# HighPowerBiPolarStepperMotorSchem.net
KiCad netlist of a schematic drawn in Altium Designer
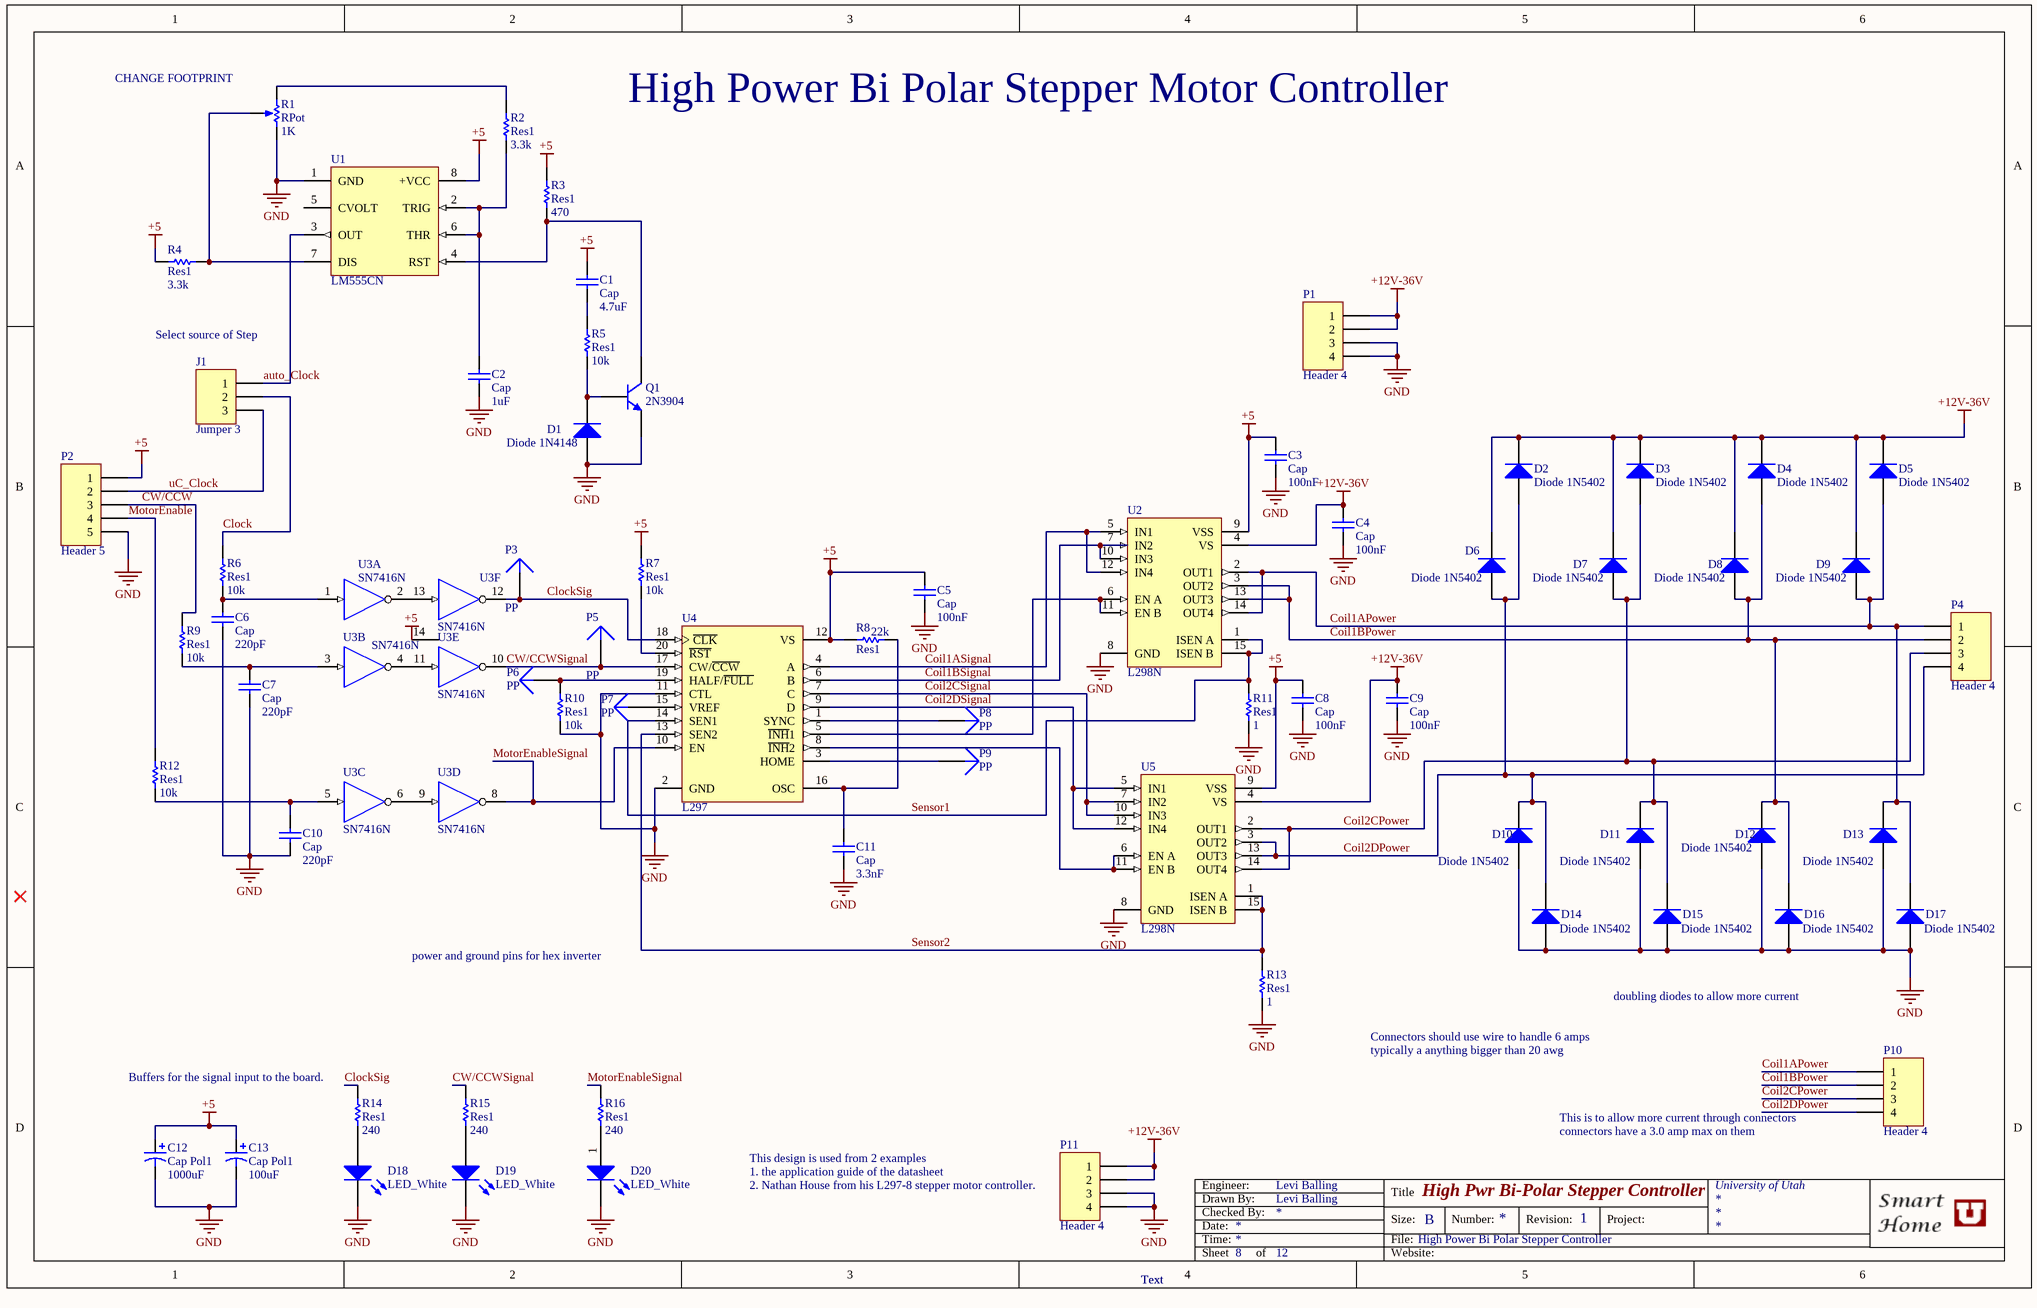
[diagram p0: HighPowerBiPolarStepperMotorSchem.SchDoc]

(export (version "E")
  (design (tool "Eeschema 10.0.6"))
  (components
    (comp (ref "C1")
      (value "Cap")
      (footprint "RAD-0.2")
      (description "Capacitor")
      (fields (field (name "ALTIUM_VALUE") "4.7uF") (field (name "PUBLISHER") "Altium Limited"))
      (libsource (lib "Miscellaneous Devices") (part "Cap"))
    )
    (comp (ref "C2")
      (value "Cap")
      (footprint "RAD-0.2")
      (description "Capacitor")
      (fields (field (name "ALTIUM_VALUE") "1uF") (field (name "PUBLISHER") "Altium Limited"))
      (libsource (lib "Miscellaneous Devices") (part "Cap"))
    )
    (comp (ref "C3")
      (value "Cap")
      (footprint "RAD-0.2")
      (description "Capacitor")
      (fields (field (name "ALTIUM_VALUE") "100nF") (field (name "PUBLISHER") "Altium Limited"))
      (libsource (lib "Miscellaneous Devices") (part "Cap"))
    )
    (comp (ref "C4")
      (value "Cap")
      (footprint "RAD-0.2")
      (description "Capacitor")
      (fields (field (name "ALTIUM_VALUE") "100nF") (field (name "PUBLISHER") "Altium Limited"))
      (libsource (lib "Miscellaneous Devices") (part "Cap"))
    )
    (comp (ref "C5")
      (value "Cap")
      (footprint "RAD-0.2")
      (description "Capacitor")
      (fields (field (name "ALTIUM_VALUE") "100nF") (field (name "PUBLISHER") "Altium Limited"))
      (libsource (lib "Miscellaneous Devices") (part "Cap"))
    )
    (comp (ref "C6")
      (value "Cap")
      (footprint "RAD-0.2")
      (description "Capacitor")
      (fields (field (name "ALTIUM_VALUE") "220pF") (field (name "PUBLISHER") "Altium Limited"))
      (libsource (lib "Miscellaneous Devices") (part "Cap"))
    )
    (comp (ref "C7")
      (value "Cap")
      (footprint "RAD-0.2")
      (description "Capacitor")
      (fields (field (name "ALTIUM_VALUE") "220pF") (field (name "PUBLISHER") "Altium Limited"))
      (libsource (lib "Miscellaneous Devices") (part "Cap"))
    )
    (comp (ref "C8")
      (value "Cap")
      (footprint "RAD-0.2")
      (description "Capacitor")
      (fields (field (name "ALTIUM_VALUE") "100nF") (field (name "PUBLISHER") "Altium Limited"))
      (libsource (lib "Miscellaneous Devices") (part "Cap"))
    )
    (comp (ref "C9")
      (value "Cap")
      (footprint "RAD-0.2")
      (description "Capacitor")
      (fields (field (name "ALTIUM_VALUE") "100nF") (field (name "PUBLISHER") "Altium Limited"))
      (libsource (lib "Miscellaneous Devices") (part "Cap"))
    )
    (comp (ref "C10")
      (value "Cap")
      (footprint "RAD-0.2")
      (description "Capacitor")
      (fields (field (name "ALTIUM_VALUE") "220pF") (field (name "PUBLISHER") "Altium Limited"))
      (libsource (lib "Miscellaneous Devices") (part "Cap"))
    )
    (comp (ref "C11")
      (value "Cap")
      (footprint "RAD-0.2")
      (description "Capacitor")
      (fields (field (name "ALTIUM_VALUE") "3.3nF") (field (name "PUBLISHER") "Altium Limited"))
      (libsource (lib "Miscellaneous Devices") (part "Cap"))
    )
    (comp (ref "C12")
      (value "Cap Pol1")
      (footprint "RB7.6-15")
      (description "Polarized Capacitor (Radial)")
      (fields (field (name "ALTIUM_VALUE") "1000uF") (field (name "PUBLISHER") "Altium Limited"))
      (libsource (lib "Miscellaneous Devices") (part "Cap Pol1"))
    )
    (comp (ref "C13")
      (value "Cap Pol1")
      (footprint "RB7.6-15")
      (description "Polarized Capacitor (Radial)")
      (fields (field (name "ALTIUM_VALUE") "100uF") (field (name "PUBLISHER") "Altium Limited"))
      (libsource (lib "Miscellaneous Devices") (part "Cap Pol1"))
    )
    (comp (ref "D1")
      (value "Diode 1N4148")
      (footprint "DO-35")
      (description "High Conductance Fast Diode")
      (fields (field (name "PUBLISHER") "Altium Limited"))
      (libsource (lib "Miscellaneous Devices") (part "Diode 1N4148"))
    )
    (comp (ref "D2")
      (value "Diode 1N5402")
      (footprint "DO-201AD")
      (description "3 Amp General Purpose Rectifier")
      (fields (field (name "PUBLISHER") "Altium Limited"))
      (libsource (lib "Miscellaneous Devices") (part "Diode 1N5402"))
    )
    (comp (ref "D3")
      (value "Diode 1N5402")
      (footprint "DO-201AD")
      (description "3 Amp General Purpose Rectifier")
      (fields (field (name "PUBLISHER") "Altium Limited"))
      (libsource (lib "Miscellaneous Devices") (part "Diode 1N5402"))
    )
    (comp (ref "D4")
      (value "Diode 1N5402")
      (footprint "DO-201AD")
      (description "3 Amp General Purpose Rectifier")
      (fields (field (name "PUBLISHER") "Altium Limited"))
      (libsource (lib "Miscellaneous Devices") (part "Diode 1N5402"))
    )
    (comp (ref "D5")
      (value "Diode 1N5402")
      (footprint "DO-201AD")
      (description "3 Amp General Purpose Rectifier")
      (fields (field (name "PUBLISHER") "Altium Limited"))
      (libsource (lib "Miscellaneous Devices") (part "Diode 1N5402"))
    )
    (comp (ref "D6")
      (value "Diode 1N5402")
      (footprint "DO-201AD")
      (description "3 Amp General Purpose Rectifier")
      (fields (field (name "PUBLISHER") "Altium Limited"))
      (libsource (lib "Miscellaneous Devices") (part "Diode 1N5402"))
    )
    (comp (ref "D7")
      (value "Diode 1N5402")
      (footprint "DO-201AD")
      (description "3 Amp General Purpose Rectifier")
      (fields (field (name "PUBLISHER") "Altium Limited"))
      (libsource (lib "Miscellaneous Devices") (part "Diode 1N5402"))
    )
    (comp (ref "D8")
      (value "Diode 1N5402")
      (footprint "DO-201AD")
      (description "3 Amp General Purpose Rectifier")
      (fields (field (name "PUBLISHER") "Altium Limited"))
      (libsource (lib "Miscellaneous Devices") (part "Diode 1N5402"))
    )
    (comp (ref "D9")
      (value "Diode 1N5402")
      (footprint "DO-201AD")
      (description "3 Amp General Purpose Rectifier")
      (fields (field (name "PUBLISHER") "Altium Limited"))
      (libsource (lib "Miscellaneous Devices") (part "Diode 1N5402"))
    )
    (comp (ref "D10")
      (value "Diode 1N5402")
      (footprint "DO-201AD")
      (description "3 Amp General Purpose Rectifier")
      (fields (field (name "PUBLISHER") "Altium Limited"))
      (libsource (lib "Miscellaneous Devices") (part "Diode 1N5402"))
    )
    (comp (ref "D11")
      (value "Diode 1N5402")
      (footprint "DO-201AD")
      (description "3 Amp General Purpose Rectifier")
      (fields (field (name "PUBLISHER") "Altium Limited"))
      (libsource (lib "Miscellaneous Devices") (part "Diode 1N5402"))
    )
    (comp (ref "D12")
      (value "Diode 1N5402")
      (footprint "DO-201AD")
      (description "3 Amp General Purpose Rectifier")
      (fields (field (name "PUBLISHER") "Altium Limited"))
      (libsource (lib "Miscellaneous Devices") (part "Diode 1N5402"))
    )
    (comp (ref "D13")
      (value "Diode 1N5402")
      (footprint "DO-201AD")
      (description "3 Amp General Purpose Rectifier")
      (fields (field (name "PUBLISHER") "Altium Limited"))
      (libsource (lib "Miscellaneous Devices") (part "Diode 1N5402"))
    )
    (comp (ref "D14")
      (value "Diode 1N5402")
      (footprint "DO-201AD")
      (description "3 Amp General Purpose Rectifier")
      (fields (field (name "PUBLISHER") "Altium Limited"))
      (libsource (lib "Miscellaneous Devices") (part "Diode 1N5402"))
    )
    (comp (ref "D15")
      (value "Diode 1N5402")
      (footprint "DO-201AD")
      (description "3 Amp General Purpose Rectifier")
      (fields (field (name "PUBLISHER") "Altium Limited"))
      (libsource (lib "Miscellaneous Devices") (part "Diode 1N5402"))
    )
    (comp (ref "D16")
      (value "Diode 1N5402")
      (footprint "DO-201AD")
      (description "3 Amp General Purpose Rectifier")
      (fields (field (name "PUBLISHER") "Altium Limited"))
      (libsource (lib "Miscellaneous Devices") (part "Diode 1N5402"))
    )
    (comp (ref "D17")
      (value "Diode 1N5402")
      (footprint "DO-201AD")
      (description "3 Amp General Purpose Rectifier")
      (fields (field (name "PUBLISHER") "Altium Limited"))
      (libsource (lib "Miscellaneous Devices") (part "Diode 1N5402"))
    )
    (comp (ref "D18")
      (value "LED_White")
      (footprint "LED")
      (description "Typical INFRARED GaAs LED")
      (fields (field (name "PUBLISHER") "Altium Limited"))
      (libsource (lib "Miscellaneous Devices") (part "LED0"))
    )
    (comp (ref "D19")
      (value "LED_White")
      (footprint "LED")
      (description "Typical INFRARED GaAs LED")
      (fields (field (name "PUBLISHER") "Altium Limited"))
      (libsource (lib "Miscellaneous Devices") (part "LED0"))
    )
    (comp (ref "D20")
      (value "LED_White")
      (footprint "LED")
      (description "Typical INFRARED GaAs LED")
      (fields (field (name "PUBLISHER") "Altium Limited"))
      (libsource (lib "") (part "LED0_1"))
    )
    (comp (ref "J1")
      (value "Jumper 3")
      (footprint "HDR1X3")
      (description "Header, 3-Pin")
      (fields (field (name "PUBLISHER") "Altium Limited"))
      (libsource (lib "Miscellaneous Connectors") (part "Header 3"))
    )
    (comp (ref "P1")
      (value "Header 4")
      (footprint "HDR1X4")
      (description "Header, 4-Pin")
      (fields (field (name "PUBLISHER") "Altium Limited"))
      (libsource (lib "Miscellaneous Connectors") (part "Header 4"))
    )
    (comp (ref "P2")
      (value "Header 5")
      (footprint "HDR1X5")
      (description "Header, 5-Pin")
      (fields (field (name "PUBLISHER") "Altium Limited"))
      (libsource (lib "Miscellaneous Connectors") (part "Header 5"))
    )
    (comp (ref "P3")
      (value "PP")
      (footprint "PIN1")
      (description "Plug")
      (fields (field (name "PUBLISHER") "Altium Limited"))
      (libsource (lib "Miscellaneous Connectors") (part "Plug"))
    )
    (comp (ref "P4")
      (value "Header 4")
      (footprint "HDR1X4")
      (description "Header, 4-Pin")
      (fields (field (name "PUBLISHER") "Altium Limited"))
      (libsource (lib "") (part "Header 4_1"))
    )
    (comp (ref "P5")
      (value "PP")
      (footprint "PIN1")
      (description "Plug")
      (fields (field (name "PUBLISHER") "Altium Limited"))
      (libsource (lib "Miscellaneous Connectors") (part "Plug"))
    )
    (comp (ref "P6")
      (value "PP")
      (footprint "PIN1")
      (description "Plug")
      (fields (field (name "PUBLISHER") "Altium Limited"))
      (libsource (lib "Miscellaneous Connectors") (part "Plug"))
    )
    (comp (ref "P7")
      (value "PP")
      (footprint "PIN1")
      (description "Plug")
      (fields (field (name "PUBLISHER") "Altium Limited"))
      (libsource (lib "Miscellaneous Connectors") (part "Plug"))
    )
    (comp (ref "P8")
      (value "PP")
      (footprint "PIN1")
      (description "Plug")
      (fields (field (name "PUBLISHER") "Altium Limited"))
      (libsource (lib "Miscellaneous Connectors") (part "Plug"))
    )
    (comp (ref "P9")
      (value "PP")
      (footprint "PIN1")
      (description "Plug")
      (fields (field (name "PUBLISHER") "Altium Limited"))
      (libsource (lib "Miscellaneous Connectors") (part "Plug"))
    )
    (comp (ref "P10")
      (value "Header 4")
      (footprint "HDR1X4")
      (description "Header, 4-Pin")
      (fields (field (name "PUBLISHER") "Altium Limited"))
      (libsource (lib "") (part "Header 4_1"))
    )
    (comp (ref "P11")
      (value "Header 4")
      (footprint "HDR1X4")
      (description "Header, 4-Pin")
      (fields (field (name "PUBLISHER") "Altium Limited"))
      (libsource (lib "Miscellaneous Connectors") (part "Header 4"))
    )
    (comp (ref "Q1")
      (value "2N3904")
      (footprint "2N3904")
      (description "NPN General Purpose Amplifier")
      (fields (field (name "PUBLISHER") "Altium Limited"))
      (libsource (lib "Miscellaneous Devices") (part "2N3904"))
    )
    (comp (ref "R1")
      (value "RPot")
      (footprint "Variable_Resistor")
      (description "Potentiometer")
      (fields (field (name "ALTIUM_VALUE") "1K") (field (name "PUBLISHER") "Altium Limited"))
      (libsource (lib "Miscellaneous Devices") (part "RPot"))
    )
    (comp (ref "R2")
      (value "Res1")
      (footprint "AXIAL-0.3")
      (description "Resistor")
      (fields (field (name "ALTIUM_VALUE") "3.3k") (field (name "PUBLISHER") "Altium Limited"))
      (libsource (lib "Miscellaneous Devices") (part "Res1"))
    )
    (comp (ref "R3")
      (value "Res1")
      (footprint "AXIAL-0.3")
      (description "Resistor")
      (fields (field (name "ALTIUM_VALUE") "470") (field (name "PUBLISHER") "Altium Limited"))
      (libsource (lib "Miscellaneous Devices") (part "Res1"))
    )
    (comp (ref "R4")
      (value "Res1")
      (footprint "AXIAL-0.3")
      (description "Resistor")
      (fields (field (name "ALTIUM_VALUE") "3.3k") (field (name "PUBLISHER") "Altium Limited"))
      (libsource (lib "Miscellaneous Devices") (part "Res1"))
    )
    (comp (ref "R5")
      (value "Res1")
      (footprint "AXIAL-0.3")
      (description "Resistor")
      (fields (field (name "ALTIUM_VALUE") "10k") (field (name "PUBLISHER") "Altium Limited"))
      (libsource (lib "Miscellaneous Devices") (part "Res1"))
    )
    (comp (ref "R6")
      (value "Res1")
      (footprint "AXIAL-0.3")
      (description "Resistor")
      (fields (field (name "ALTIUM_VALUE") "10k") (field (name "PUBLISHER") "Altium Limited"))
      (libsource (lib "Miscellaneous Devices") (part "Res1"))
    )
    (comp (ref "R7")
      (value "Res1")
      (footprint "AXIAL-0.3")
      (description "Resistor")
      (fields (field (name "ALTIUM_VALUE") "10k") (field (name "PUBLISHER") "Altium Limited"))
      (libsource (lib "Miscellaneous Devices") (part "Res1"))
    )
    (comp (ref "R8")
      (value "Res1")
      (footprint "AXIAL-0.3")
      (description "Resistor")
      (fields (field (name "ALTIUM_VALUE") "22k") (field (name "PUBLISHER") "Altium Limited"))
      (libsource (lib "Miscellaneous Devices") (part "Res1"))
    )
    (comp (ref "R9")
      (value "Res1")
      (footprint "AXIAL-0.3")
      (description "Resistor")
      (fields (field (name "ALTIUM_VALUE") "10k") (field (name "PUBLISHER") "Altium Limited"))
      (libsource (lib "Miscellaneous Devices") (part "Res1"))
    )
    (comp (ref "R10")
      (value "Res1")
      (footprint "AXIAL-0.3")
      (description "Resistor")
      (fields (field (name "ALTIUM_VALUE") "10k") (field (name "PUBLISHER") "Altium Limited"))
      (libsource (lib "Miscellaneous Devices") (part "Res1"))
    )
    (comp (ref "R11")
      (value "Res1")
      (footprint "AXIAL-1.0")
      (description "Resistor")
      (fields (field (name "ALTIUM_VALUE") "1") (field (name "PUBLISHER") "Altium Limited"))
      (libsource (lib "Miscellaneous Devices") (part "Res1"))
    )
    (comp (ref "R12")
      (value "Res1")
      (footprint "AXIAL-0.3")
      (description "Resistor")
      (fields (field (name "ALTIUM_VALUE") "10k") (field (name "PUBLISHER") "Altium Limited"))
      (libsource (lib "Miscellaneous Devices") (part "Res1"))
    )
    (comp (ref "R13")
      (value "Res1")
      (footprint "AXIAL-1.0")
      (description "Resistor")
      (fields (field (name "ALTIUM_VALUE") "1") (field (name "PUBLISHER") "Altium Limited"))
      (libsource (lib "Miscellaneous Devices") (part "Res1"))
    )
    (comp (ref "R14")
      (value "Res1")
      (footprint "AXIAL-0.3")
      (description "Resistor")
      (fields (field (name "ALTIUM_VALUE") "240") (field (name "PUBLISHER") "Altium Limited"))
      (libsource (lib "Miscellaneous Devices") (part "Res1"))
    )
    (comp (ref "R15")
      (value "Res1")
      (footprint "AXIAL-0.3")
      (description "Resistor")
      (fields (field (name "ALTIUM_VALUE") "240") (field (name "PUBLISHER") "Altium Limited"))
      (libsource (lib "Miscellaneous Devices") (part "Res1"))
    )
    (comp (ref "R16")
      (value "Res1")
      (footprint "AXIAL-0.3")
      (description "Resistor")
      (fields (field (name "ALTIUM_VALUE") "240") (field (name "PUBLISHER") "Altium Limited"))
      (libsource (lib "Miscellaneous Devices") (part "Res1"))
    )
    (comp (ref "U1")
      (value "LM555CN")
      (footprint "N08E")
      (description "Timer")
      (fields
        (field (name "MANUFACTURER") "National Semiconductor")
        (field (name "DIGIKEYPARTNUMBER") "LM555CNNS-ND")
        (field (name "PUBLISHER") "Altium Limited")
      )
      (libsource (lib "NSC Analog") (part "LM555CN"))
    )
    (comp (ref "U2")
      (value "L298N")
      (footprint "Multiwatt15V")
      (description "Dual Full Bridge Driver")
      (fields (field (name "PUBLISHER") "Altium Limited"))
      (libsource (lib "ST Interface DC Motor Controller") (part "L298N"))
    )
    (comp (ref "U3")
      (value "SN7416N")
      (footprint "N014")
      (description "Hex Inverter Buffer / Driver with High-Voltage Outputs")
      (fields (field (name "PUBLISHER") "Altium Limited"))
      (libsource (lib "TI Logic Gate 1") (part "SN7416N"))
    )
    (comp (ref "U4")
      (value "L297")
      (footprint "DIP20")
      (description "Stepper Motor Controller")
      (fields (field (name "PUBLISHER") "Altium Limited"))
      (libsource (lib "ST Interface Stepper Motor Controller") (part "L297"))
    )
    (comp (ref "U5")
      (value "L298N")
      (footprint "Multiwatt15V")
      (description "Dual Full Bridge Driver")
      (fields (field (name "PUBLISHER") "Altium Limited"))
      (libsource (lib "ST Interface DC Motor Controller") (part "L298N"))
    )
  )
  (nets
    (net (code "1") (name "+5") (class "Default")
      (node (ref "C1") (pin "2") (pinfunction "2_2") (pintype "passive"))
      (node (ref "C12") (pin "1") (pinfunction "1_1") (pintype "passive"))
      (node (ref "C13") (pin "1") (pinfunction "1_1") (pintype "passive"))
      (node (ref "C3") (pin "2") (pinfunction "2_2") (pintype "passive"))
      (node (ref "C5") (pin "2") (pinfunction "2_2") (pintype "passive"))
      (node (ref "C8") (pin "2") (pinfunction "2_2") (pintype "passive"))
      (node (ref "P2") (pin "1") (pinfunction "1_1") (pintype "passive"))
      (node (ref "R3") (pin "1") (pinfunction "1_1") (pintype "passive"))
      (node (ref "R4") (pin "2") (pinfunction "2_2") (pintype "passive"))
      (node (ref "R7") (pin "2") (pinfunction "2_2") (pintype "passive"))
      (node (ref "R8") (pin "1") (pinfunction "1_1") (pintype "passive"))
      (node (ref "U1") (pin "8") (pinfunction "+VCC_8") (pintype "power_in"))
      (node (ref "U2") (pin "9") (pinfunction "VSS_9") (pintype "power_in"))
      (node (ref "U3") (pin "14") (pinfunction "VCC_14") (pintype "power_in"))
      (node (ref "U4") (pin "12") (pinfunction "VS_12") (pintype "power_in"))
      (node (ref "U5") (pin "9") (pinfunction "VSS_9") (pintype "power_in"))
    )
    (net (code "2") (name "+12V-36V") (class "Default")
      (node (ref "C4") (pin "2") (pinfunction "2_2") (pintype "passive"))
      (node (ref "C9") (pin "2") (pinfunction "2_2") (pintype "passive"))
      (node (ref "D2") (pin "2") (pinfunction "K_2") (pintype "passive"))
      (node (ref "D3") (pin "2") (pinfunction "K_2") (pintype "passive"))
      (node (ref "D4") (pin "2") (pinfunction "K_2") (pintype "passive"))
      (node (ref "D5") (pin "2") (pinfunction "K_2") (pintype "passive"))
      (node (ref "D6") (pin "2") (pinfunction "K_2") (pintype "passive"))
      (node (ref "D7") (pin "2") (pinfunction "K_2") (pintype "passive"))
      (node (ref "D8") (pin "2") (pinfunction "K_2") (pintype "passive"))
      (node (ref "D9") (pin "2") (pinfunction "K_2") (pintype "passive"))
      (node (ref "P1") (pin "1") (pinfunction "1_1") (pintype "passive"))
      (node (ref "P1") (pin "2") (pinfunction "2_2") (pintype "passive"))
      (node (ref "P11") (pin "1") (pinfunction "1_1") (pintype "passive"))
      (node (ref "P11") (pin "2") (pinfunction "2_2") (pintype "passive"))
      (node (ref "U2") (pin "4") (pinfunction "VS_4") (pintype "power_in"))
      (node (ref "U5") (pin "4") (pinfunction "VS_4") (pintype "power_in"))
    )
    (net (code "3") (name "/CW{slash}CCW") (class "Default")
      (node (ref "P2") (pin "3") (pinfunction "3_3") (pintype "passive"))
      (node (ref "R9") (pin "1") (pinfunction "1_1") (pintype "passive"))
    )
    (net (code "4") (name "/CW{slash}CCWSignal") (class "Default")
      (node (ref "P5") (pin "1") (pinfunction "1_1") (pintype "passive"))
      (node (ref "R15") (pin "1") (pinfunction "1_1") (pintype "passive"))
      (node (ref "U3") (pin "10") (pinfunction "Y_10") (pintype "open_collector"))
      (node (ref "U4") (pin "17") (pinfunction "CW/~{CCW}_17") (pintype "input"))
    )
    (net (code "5") (name "/Clock") (class "Default")
      (node (ref "J1") (pin "2") (pinfunction "2_2") (pintype "passive"))
      (node (ref "R6") (pin "1") (pinfunction "1_1") (pintype "passive"))
    )
    (net (code "6") (name "/ClockSig") (class "Default")
      (node (ref "P3") (pin "1") (pinfunction "1_1") (pintype "passive"))
      (node (ref "R14") (pin "1") (pinfunction "1_1") (pintype "passive"))
      (node (ref "U3") (pin "12") (pinfunction "Y_12") (pintype "open_collector"))
      (node (ref "U4") (pin "18") (pinfunction "~{CLK}_18") (pintype "input"))
    )
    (net (code "7") (name "/Coil1APower") (class "Default")
      (node (ref "D13") (pin "2") (pinfunction "K_2") (pintype "passive"))
      (node (ref "D17") (pin "2") (pinfunction "K_2") (pintype "passive"))
      (node (ref "D5") (pin "1") (pinfunction "A_1") (pintype "passive"))
      (node (ref "D9") (pin "1") (pinfunction "A_1") (pintype "passive"))
      (node (ref "P10") (pin "1") (pinfunction "1_1") (pintype "passive"))
      (node (ref "P4") (pin "1") (pinfunction "1_1") (pintype "passive"))
      (node (ref "U2") (pin "14") (pinfunction "OUT4_14") (pintype "output"))
      (node (ref "U2") (pin "2") (pinfunction "OUT1_2") (pintype "output"))
    )
    (net (code "8") (name "/Coil1ASignal") (class "Default")
      (node (ref "U2") (pin "12") (pinfunction "IN4_12") (pintype "input"))
      (node (ref "U2") (pin "5") (pinfunction "IN1_5") (pintype "input"))
      (node (ref "U4") (pin "4") (pinfunction "A_4") (pintype "output"))
    )
    (net (code "9") (name "/Coil1BPower") (class "Default")
      (node (ref "D12") (pin "2") (pinfunction "K_2") (pintype "passive"))
      (node (ref "D16") (pin "2") (pinfunction "K_2") (pintype "passive"))
      (node (ref "D4") (pin "1") (pinfunction "A_1") (pintype "passive"))
      (node (ref "D8") (pin "1") (pinfunction "A_1") (pintype "passive"))
      (node (ref "P10") (pin "2") (pinfunction "2_2") (pintype "passive"))
      (node (ref "P4") (pin "2") (pinfunction "2_2") (pintype "passive"))
      (node (ref "U2") (pin "13") (pinfunction "OUT3_13") (pintype "output"))
      (node (ref "U2") (pin "3") (pinfunction "OUT2_3") (pintype "output"))
    )
    (net (code "10") (name "/Coil1BSignal") (class "Default")
      (node (ref "U2") (pin "10") (pinfunction "IN3_10") (pintype "input"))
      (node (ref "U2") (pin "7") (pinfunction "IN2_7") (pintype "input"))
      (node (ref "U4") (pin "6") (pinfunction "B_6") (pintype "output"))
    )
    (net (code "11") (name "/Coil2CPower") (class "Default")
      (node (ref "D11") (pin "2") (pinfunction "K_2") (pintype "passive"))
      (node (ref "D15") (pin "2") (pinfunction "K_2") (pintype "passive"))
      (node (ref "D3") (pin "1") (pinfunction "A_1") (pintype "passive"))
      (node (ref "D7") (pin "1") (pinfunction "A_1") (pintype "passive"))
      (node (ref "P10") (pin "3") (pinfunction "3_3") (pintype "passive"))
      (node (ref "P4") (pin "3") (pinfunction "3_3") (pintype "passive"))
      (node (ref "U5") (pin "14") (pinfunction "OUT4_14") (pintype "output"))
      (node (ref "U5") (pin "2") (pinfunction "OUT1_2") (pintype "output"))
    )
    (net (code "12") (name "/Coil2CSignal") (class "Default")
      (node (ref "U4") (pin "7") (pinfunction "C_7") (pintype "output"))
      (node (ref "U5") (pin "10") (pinfunction "IN3_10") (pintype "input"))
      (node (ref "U5") (pin "7") (pinfunction "IN2_7") (pintype "input"))
    )
    (net (code "13") (name "/Coil2DPower") (class "Default")
      (node (ref "D10") (pin "2") (pinfunction "K_2") (pintype "passive"))
      (node (ref "D14") (pin "2") (pinfunction "K_2") (pintype "passive"))
      (node (ref "D2") (pin "1") (pinfunction "A_1") (pintype "passive"))
      (node (ref "D6") (pin "1") (pinfunction "A_1") (pintype "passive"))
      (node (ref "P10") (pin "4") (pinfunction "4_4") (pintype "passive"))
      (node (ref "P4") (pin "4") (pinfunction "4_4") (pintype "passive"))
      (node (ref "U5") (pin "13") (pinfunction "OUT3_13") (pintype "output"))
      (node (ref "U5") (pin "3") (pinfunction "OUT2_3") (pintype "output"))
    )
    (net (code "14") (name "/Coil2DSignal") (class "Default")
      (node (ref "U4") (pin "9") (pinfunction "D_9") (pintype "output"))
      (node (ref "U5") (pin "12") (pinfunction "IN4_12") (pintype "input"))
      (node (ref "U5") (pin "5") (pinfunction "IN1_5") (pintype "input"))
    )
    (net (code "15") (name "/MotorEnable") (class "Default")
      (node (ref "P2") (pin "4") (pinfunction "4_4") (pintype "passive"))
      (node (ref "R12") (pin "2") (pinfunction "2_2") (pintype "passive"))
    )
    (net (code "16") (name "/MotorEnableSignal") (class "Default")
      (node (ref "R16") (pin "1") (pinfunction "1_1") (pintype "passive"))
      (node (ref "U3") (pin "8") (pinfunction "Y_8") (pintype "open_collector"))
      (node (ref "U4") (pin "10") (pinfunction "EN_10") (pintype "input"))
    )
    (net (code "17") (name "/Sensor1") (class "Default")
      (node (ref "R11") (pin "2") (pinfunction "2_2") (pintype "passive"))
      (node (ref "U2") (pin "1") (pinfunction "ISEN_A_1") (pintype "passive"))
      (node (ref "U2") (pin "15") (pinfunction "ISEN_B_15") (pintype "passive"))
      (node (ref "U4") (pin "14") (pinfunction "SEN1_14") (pintype "input"))
    )
    (net (code "18") (name "/Sensor2") (class "Default")
      (node (ref "R13") (pin "2") (pinfunction "2_2") (pintype "passive"))
      (node (ref "U4") (pin "13") (pinfunction "SEN2_13") (pintype "input"))
      (node (ref "U5") (pin "1") (pinfunction "ISEN_A_1") (pintype "passive"))
      (node (ref "U5") (pin "15") (pinfunction "ISEN_B_15") (pintype "passive"))
    )
    (net (code "19") (name "/auto_Clock") (class "Default")
      (node (ref "J1") (pin "1") (pinfunction "1_1") (pintype "passive"))
      (node (ref "U1") (pin "3") (pinfunction "OUT_3") (pintype "output"))
    )
    (net (code "20") (name "/uC_Clock") (class "Default")
      (node (ref "J1") (pin "3") (pinfunction "3_3") (pintype "passive"))
      (node (ref "P2") (pin "2") (pinfunction "2_2") (pintype "passive"))
    )
    (net (code "21") (name "GND") (class "Default")
      (node (ref "C10") (pin "1") (pinfunction "1_1") (pintype "passive"))
      (node (ref "C11") (pin "1") (pinfunction "1_1") (pintype "passive"))
      (node (ref "C12") (pin "2") (pinfunction "2_2") (pintype "passive"))
      (node (ref "C13") (pin "2") (pinfunction "2_2") (pintype "passive"))
      (node (ref "C2") (pin "1") (pinfunction "1_1") (pintype "passive"))
      (node (ref "C3") (pin "1") (pinfunction "1_1") (pintype "passive"))
      (node (ref "C4") (pin "1") (pinfunction "1_1") (pintype "passive"))
      (node (ref "C5") (pin "1") (pinfunction "1_1") (pintype "passive"))
      (node (ref "C6") (pin "1") (pinfunction "1_1") (pintype "passive"))
      (node (ref "C7") (pin "1") (pinfunction "1_1") (pintype "passive"))
      (node (ref "C8") (pin "1") (pinfunction "1_1") (pintype "passive"))
      (node (ref "C9") (pin "1") (pinfunction "1_1") (pintype "passive"))
      (node (ref "D1") (pin "1") (pinfunction "A_1") (pintype "passive"))
      (node (ref "D10") (pin "1") (pinfunction "A_1") (pintype "passive"))
      (node (ref "D11") (pin "1") (pinfunction "A_1") (pintype "passive"))
      (node (ref "D12") (pin "1") (pinfunction "A_1") (pintype "passive"))
      (node (ref "D13") (pin "1") (pinfunction "A_1") (pintype "passive"))
      (node (ref "D14") (pin "1") (pinfunction "A_1") (pintype "passive"))
      (node (ref "D15") (pin "1") (pinfunction "A_1") (pintype "passive"))
      (node (ref "D16") (pin "1") (pinfunction "A_1") (pintype "passive"))
      (node (ref "D17") (pin "1") (pinfunction "A_1") (pintype "passive"))
      (node (ref "D18") (pin "2") (pinfunction "K_2") (pintype "passive"))
      (node (ref "D19") (pin "2") (pinfunction "K_2") (pintype "passive"))
      (node (ref "D20") (pin "2") (pinfunction "K_2") (pintype "passive"))
      (node (ref "P1") (pin "3") (pinfunction "3_3") (pintype "passive"))
      (node (ref "P1") (pin "4") (pinfunction "4_4") (pintype "passive"))
      (node (ref "P11") (pin "3") (pinfunction "3_3") (pintype "passive"))
      (node (ref "P11") (pin "4") (pinfunction "4_4") (pintype "passive"))
      (node (ref "P2") (pin "5") (pinfunction "5_5") (pintype "passive"))
      (node (ref "Q1") (pin "1") (pinfunction "E_1") (pintype "passive"))
      (node (ref "R1") (pin "2") (pinfunction "BOT_2") (pintype "passive"))
      (node (ref "R10") (pin "2") (pinfunction "2_2") (pintype "passive"))
      (node (ref "R11") (pin "1") (pinfunction "1_1") (pintype "passive"))
      (node (ref "R13") (pin "1") (pinfunction "1_1") (pintype "passive"))
      (node (ref "U1") (pin "1") (pinfunction "GND_1") (pintype "power_in"))
      (node (ref "U2") (pin "8") (pinfunction "GND_8") (pintype "power_in"))
      (node (ref "U3") (pin "7") (pinfunction "GND_7") (pintype "power_in"))
      (node (ref "U4") (pin "11") (pinfunction "CTL_11") (pintype "input"))
      (node (ref "U4") (pin "2") (pinfunction "GND_2") (pintype "power_in"))
      (node (ref "U5") (pin "8") (pinfunction "GND_8") (pintype "power_in"))
    )
    (net (code "22") (name "Net-(C1-Pad1)") (class "Default")
      (node (ref "C1") (pin "1") (pinfunction "1_1") (pintype "passive"))
      (node (ref "R5") (pin "1") (pinfunction "1_1") (pintype "passive"))
    )
    (net (code "23") (name "Net-(D1-K)") (class "Default")
      (node (ref "D1") (pin "2") (pinfunction "K_2") (pintype "passive"))
      (node (ref "Q1") (pin "2") (pinfunction "B_2") (pintype "passive"))
      (node (ref "R5") (pin "2") (pinfunction "2_2") (pintype "passive"))
    )
    (net (code "24") (name "Net-(D18-A)") (class "Default")
      (node (ref "D18") (pin "1") (pinfunction "A_1") (pintype "passive"))
      (node (ref "R14") (pin "2") (pinfunction "2_2") (pintype "passive"))
    )
    (net (code "25") (name "Net-(D19-A)") (class "Default")
      (node (ref "D19") (pin "1") (pinfunction "A_1") (pintype "passive"))
      (node (ref "R15") (pin "2") (pinfunction "2_2") (pintype "passive"))
    )
    (net (code "26") (name "Net-(D20-A)") (class "Default")
      (node (ref "D20") (pin "1") (pinfunction "A_1") (pintype "passive"))
      (node (ref "R16") (pin "2") (pinfunction "2_2") (pintype "passive"))
    )
    (net (code "27") (name "Net-(Q1-C)") (class "Default")
      (node (ref "Q1") (pin "3") (pinfunction "C_3") (pintype "passive"))
      (node (ref "R3") (pin "2") (pinfunction "2_2") (pintype "passive"))
      (node (ref "U1") (pin "4") (pinfunction "RST_4") (pintype "input"))
    )
    (net (code "28") (name "Net-(R1-TAP)") (class "Default")
      (node (ref "R1") (pin "3") (pinfunction "TAP_3") (pintype "passive"))
      (node (ref "R4") (pin "1") (pinfunction "1_1") (pintype "passive"))
      (node (ref "U1") (pin "7") (pinfunction "DIS_7") (pintype "open_collector"))
    )
    (net (code "29") (name "Net-(R1-TOP)") (class "Default")
      (node (ref "R1") (pin "1") (pinfunction "TOP_1") (pintype "passive"))
      (node (ref "R2") (pin "2") (pinfunction "2_2") (pintype "passive"))
    )
    (net (code "30") (name "Net-(U1-THR)") (class "Default")
      (node (ref "C2") (pin "2") (pinfunction "2_2") (pintype "passive"))
      (node (ref "R2") (pin "1") (pinfunction "1_1") (pintype "passive"))
      (node (ref "U1") (pin "2") (pinfunction "TRIG_2") (pintype "input"))
      (node (ref "U1") (pin "6") (pinfunction "THR_6") (pintype "input"))
    )
    (net (code "31") (name "Net-(U2-EN_A)") (class "Default")
      (node (ref "U2") (pin "11") (pinfunction "EN_B_11") (pintype "input"))
      (node (ref "U2") (pin "6") (pinfunction "EN_A_6") (pintype "input"))
      (node (ref "U4") (pin "5") (pinfunction "~{INH}1_5") (pintype "output"))
    )
    (net (code "32") (name "Net-(U3A-A)") (class "Default")
      (node (ref "C6") (pin "2") (pinfunction "2_2") (pintype "passive"))
      (node (ref "R6") (pin "2") (pinfunction "2_2") (pintype "passive"))
      (node (ref "U3") (pin "1") (pinfunction "A_1") (pintype "input"))
    )
    (net (code "33") (name "Net-(U3A-Y)") (class "Default")
      (node (ref "U3") (pin "13") (pinfunction "A_13") (pintype "input"))
      (node (ref "U3") (pin "2") (pinfunction "Y_2") (pintype "open_collector"))
    )
    (net (code "34") (name "Net-(U3B-A)") (class "Default")
      (node (ref "C7") (pin "2") (pinfunction "2_2") (pintype "passive"))
      (node (ref "R9") (pin "2") (pinfunction "2_2") (pintype "passive"))
      (node (ref "U3") (pin "3") (pinfunction "A_3") (pintype "input"))
    )
    (net (code "35") (name "Net-(U3B-Y)") (class "Default")
      (node (ref "U3") (pin "11") (pinfunction "A_11") (pintype "input"))
      (node (ref "U3") (pin "4") (pinfunction "Y_4") (pintype "open_collector"))
    )
    (net (code "36") (name "Net-(U3C-A)") (class "Default")
      (node (ref "C10") (pin "2") (pinfunction "2_2") (pintype "passive"))
      (node (ref "R12") (pin "1") (pinfunction "1_1") (pintype "passive"))
      (node (ref "U3") (pin "5") (pinfunction "A_5") (pintype "input"))
    )
    (net (code "37") (name "Net-(U3C-Y)") (class "Default")
      (node (ref "U3") (pin "6") (pinfunction "Y_6") (pintype "open_collector"))
      (node (ref "U3") (pin "9") (pinfunction "A_9") (pintype "input"))
    )
    (net (code "38") (name "Net-(U4-HALF{slash}~{FULL})") (class "Default")
      (node (ref "P6") (pin "1") (pinfunction "1_1") (pintype "passive"))
      (node (ref "R10") (pin "1") (pinfunction "1_1") (pintype "passive"))
      (node (ref "U4") (pin "19") (pinfunction "HALF/~{FULL}_19") (pintype "input"))
    )
    (net (code "39") (name "Net-(U4-HOME)") (class "Default")
      (node (ref "P9") (pin "1") (pinfunction "1_1") (pintype "passive"))
      (node (ref "U4") (pin "3") (pinfunction "HOME_3") (pintype "open_collector"))
    )
    (net (code "40") (name "Net-(U4-OSC)") (class "Default")
      (node (ref "C11") (pin "2") (pinfunction "2_2") (pintype "passive"))
      (node (ref "R8") (pin "2") (pinfunction "2_2") (pintype "passive"))
      (node (ref "U4") (pin "16") (pinfunction "OSC_16") (pintype "passive"))
    )
    (net (code "41") (name "Net-(U4-SYNC)") (class "Default")
      (node (ref "P8") (pin "1") (pinfunction "1_1") (pintype "passive"))
      (node (ref "U4") (pin "1") (pinfunction "SYNC_1") (pintype "output"))
    )
    (net (code "42") (name "Net-(U4-VREF)") (class "Default")
      (node (ref "P7") (pin "1") (pinfunction "1_1") (pintype "passive"))
      (node (ref "U4") (pin "15") (pinfunction "VREF_15") (pintype "input"))
    )
    (net (code "43") (name "Net-(U4-~{INH}2)") (class "Default")
      (node (ref "U4") (pin "8") (pinfunction "~{INH}2_8") (pintype "output"))
      (node (ref "U5") (pin "11") (pinfunction "EN_B_11") (pintype "input"))
      (node (ref "U5") (pin "6") (pinfunction "EN_A_6") (pintype "input"))
    )
    (net (code "44") (name "Net-(U4-~{RST})") (class "Default")
      (node (ref "R7") (pin "1") (pinfunction "1_1") (pintype "passive"))
      (node (ref "U4") (pin "20") (pinfunction "~{RST}_20") (pintype "input"))
    )
    (net (code "45") (name "unconnected-(U1-CVOLT-Pad5)") (class "Default")
      (node (ref "U1") (pin "5") (pinfunction "CVOLT_5") (pintype "passive"))
    )
  )
)
